# SNAC_7ch_hdmi-5v.net
KiCad netlist of a schematic drawn in EAGLE
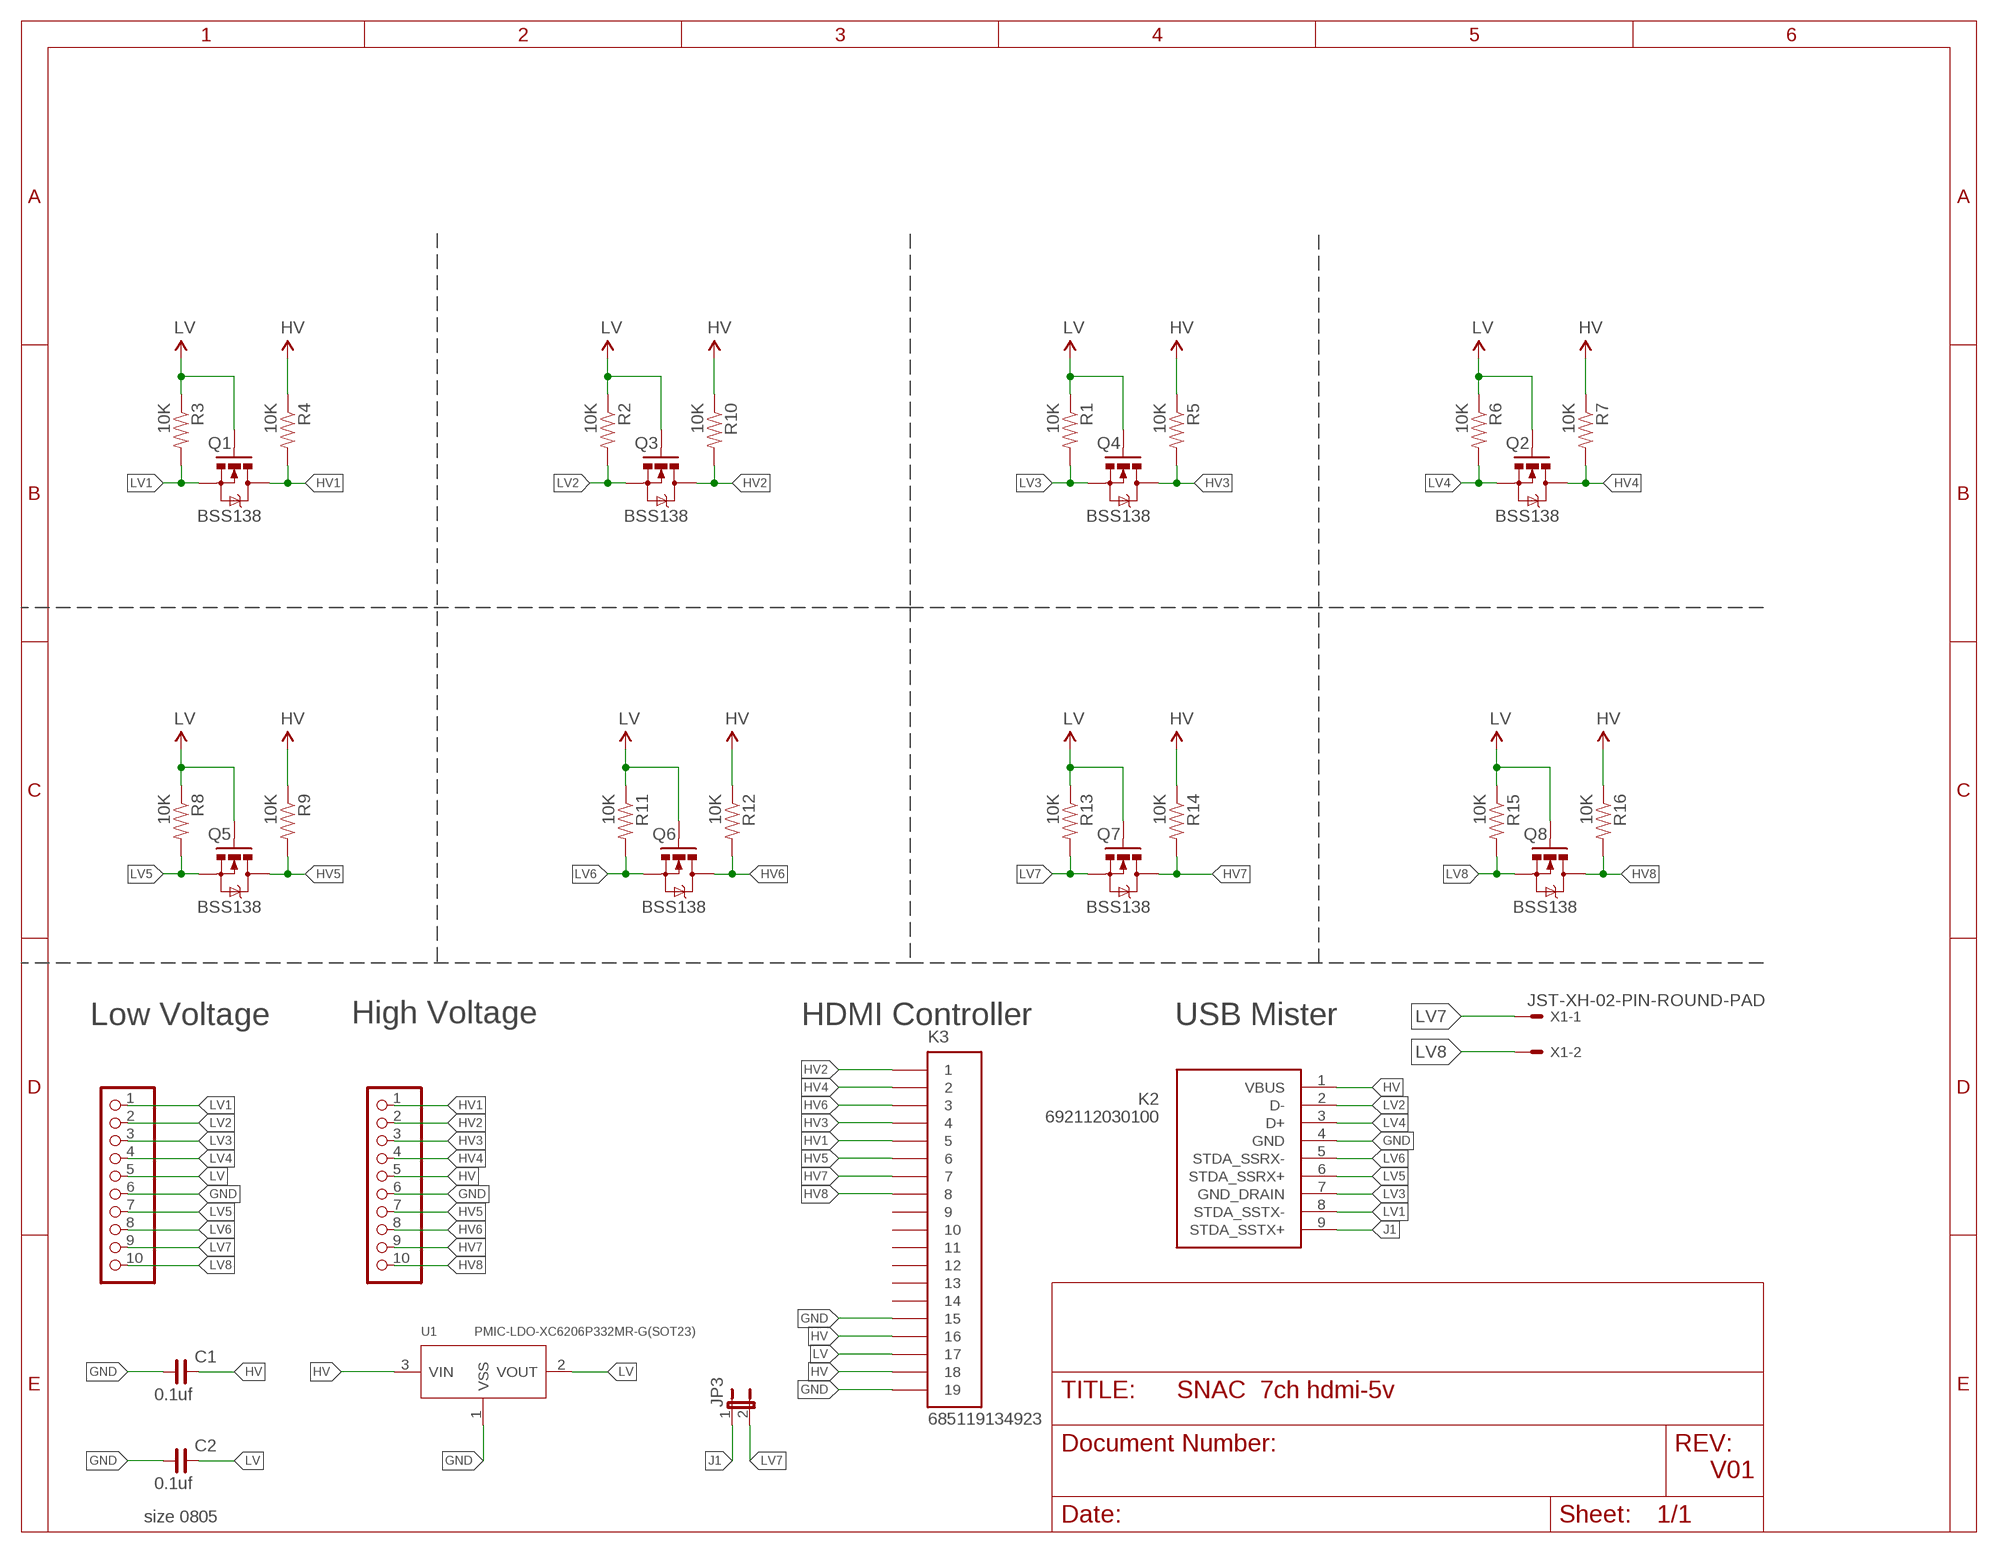
[diagram p0: schematic, sheet 1]

(export (version "E")
  (design (tool "Eeschema 10.0.6"))
  (components
    (comp (ref "C1")
      (value "0.1uf")
      (footprint "eagle-import:C0805")
      (libsource (lib "eagle-import") (part "C_0805"))
    )
    (comp (ref "C2")
      (value "0.1uf")
      (footprint "eagle-import:C0805")
      (libsource (lib "eagle-import") (part "C_0805"))
    )
    (comp (ref "JP1")
      (value "PINHD-1X10_2.54-S")
      (footprint "eagle-import:1X10-S")
      (libsource (lib "eagle-import") (part "PINHD-1X10_2.54-S"))
    )
    (comp (ref "JP2")
      (value "PINHD-1X10_2.54-S")
      (footprint "eagle-import:1X10-S")
      (libsource (lib "eagle-import") (part "PINHD-1X10_2.54-S"))
    )
    (comp (ref "JP3")
      (value "JUMPER-2PTH")
      (footprint "eagle-import:1X02")
      (libsource (lib "eagle-import") (part "JUMPER-2PTH"))
    )
    (comp (ref "K2")
      (value "692112030100")
      (footprint "eagle-import:692112030100")
      (libsource (lib "eagle-import") (part "692112030100"))
    )
    (comp (ref "K3")
      (value "685119134923")
      (footprint "eagle-import:685119134923")
      (libsource (lib "eagle-import") (part "685119134923"))
    )
    (comp (ref "Q1")
      (value "BSS138")
      (footprint "eagle-import:SOT23-3")
      (libsource (lib "eagle-import") (part "MOSFET-NCHANNELSMD"))
    )
    (comp (ref "Q2")
      (value "BSS138")
      (footprint "eagle-import:SOT23-3")
      (libsource (lib "eagle-import") (part "MOSFET-NCHANNELSMD"))
    )
    (comp (ref "Q3")
      (value "BSS138")
      (footprint "eagle-import:SOT23-3")
      (libsource (lib "eagle-import") (part "MOSFET-NCHANNELSMD"))
    )
    (comp (ref "Q4")
      (value "BSS138")
      (footprint "eagle-import:SOT23-3")
      (libsource (lib "eagle-import") (part "MOSFET-NCHANNELSMD"))
    )
    (comp (ref "Q5")
      (value "BSS138")
      (footprint "eagle-import:SOT23-3")
      (libsource (lib "eagle-import") (part "MOSFET-NCHANNELSMD"))
    )
    (comp (ref "Q6")
      (value "BSS138")
      (footprint "eagle-import:SOT23-3")
      (libsource (lib "eagle-import") (part "MOSFET-NCHANNELSMD"))
    )
    (comp (ref "Q7")
      (value "BSS138")
      (footprint "eagle-import:SOT23-3")
      (libsource (lib "eagle-import") (part "MOSFET-NCHANNELSMD"))
    )
    (comp (ref "Q8")
      (value "BSS138")
      (footprint "eagle-import:SOT23-3")
      (libsource (lib "eagle-import") (part "MOSFET-NCHANNELSMD"))
    )
    (comp (ref "R1")
      (value "10K")
      (footprint "eagle-import:0603-RES")
      (libsource (lib "eagle-import") (part "RESISTOR0603-RES"))
    )
    (comp (ref "R2")
      (value "10K")
      (footprint "eagle-import:0603-RES")
      (libsource (lib "eagle-import") (part "RESISTOR0603-RES"))
    )
    (comp (ref "R3")
      (value "10K")
      (footprint "eagle-import:0603-RES")
      (libsource (lib "eagle-import") (part "RESISTOR0603-RES"))
    )
    (comp (ref "R4")
      (value "10K")
      (footprint "eagle-import:0603-RES")
      (libsource (lib "eagle-import") (part "RESISTOR0603-RES"))
    )
    (comp (ref "R5")
      (value "10K")
      (footprint "eagle-import:0603-RES")
      (libsource (lib "eagle-import") (part "RESISTOR0603-RES"))
    )
    (comp (ref "R6")
      (value "10K")
      (footprint "eagle-import:0603-RES")
      (libsource (lib "eagle-import") (part "RESISTOR0603-RES"))
    )
    (comp (ref "R7")
      (value "10K")
      (footprint "eagle-import:0603-RES")
      (libsource (lib "eagle-import") (part "RESISTOR0603-RES"))
    )
    (comp (ref "R8")
      (value "10K")
      (footprint "eagle-import:0603-RES")
      (libsource (lib "eagle-import") (part "RESISTOR0603-RES"))
    )
    (comp (ref "R9")
      (value "10K")
      (footprint "eagle-import:0603-RES")
      (libsource (lib "eagle-import") (part "RESISTOR0603-RES"))
    )
    (comp (ref "R10")
      (value "10K")
      (footprint "eagle-import:0603-RES")
      (libsource (lib "eagle-import") (part "RESISTOR0603-RES"))
    )
    (comp (ref "R11")
      (value "10K")
      (footprint "eagle-import:0603-RES")
      (libsource (lib "eagle-import") (part "RESISTOR0603-RES"))
    )
    (comp (ref "R12")
      (value "10K")
      (footprint "eagle-import:0603-RES")
      (libsource (lib "eagle-import") (part "RESISTOR0603-RES"))
    )
    (comp (ref "R13")
      (value "10K")
      (footprint "eagle-import:0603-RES")
      (libsource (lib "eagle-import") (part "RESISTOR0603-RES"))
    )
    (comp (ref "R14")
      (value "10K")
      (footprint "eagle-import:0603-RES")
      (libsource (lib "eagle-import") (part "RESISTOR0603-RES"))
    )
    (comp (ref "R15")
      (value "10K")
      (footprint "eagle-import:0603-RES")
      (libsource (lib "eagle-import") (part "RESISTOR0603-RES"))
    )
    (comp (ref "R16")
      (value "10K")
      (footprint "eagle-import:0603-RES")
      (libsource (lib "eagle-import") (part "RESISTOR0603-RES"))
    )
    (comp (ref "U1")
      (value "PMIC-LDO-XC6206P332MR-G(SOT23)")
      (footprint "eagle-import:SOT-23")
      (fields (field (name "MF") "Torex") (field (name "MP") "XC6206P332MR-G"))
      (libsource (lib "eagle-import") (part "PMIC-LDO-XC6206P332MR-G(SOT23)"))
    )
    (comp (ref "X1")
      (value "JST-XH-02-PIN-ROUND-PAD")
      (footprint "eagle-import:JST-XH-02-PACKAGE-ROUND-PAD")
      (libsource (lib "eagle-import") (part "JST-XH-02-PIN-ROUND-PAD"))
    )
  )
  (nets
    (net (code "1") (name "GND") (class "Default")
      (node (ref "C1") (pin "1") (pinfunction "1_1") (pintype "passive"))
      (node (ref "C2") (pin "1") (pinfunction "1_1") (pintype "passive"))
      (node (ref "JP1") (pin "6") (pinfunction "6_6") (pintype "passive"))
      (node (ref "JP2") (pin "6") (pinfunction "6_6") (pintype "passive"))
      (node (ref "K2") (pin "4") (pinfunction "GND_4") (pintype "bidirectional"))
      (node (ref "K3") (pin "15") (pinfunction "15_15") (pintype "passive"))
      (node (ref "K3") (pin "19") (pinfunction "19_19") (pintype "passive"))
      (node (ref "U1") (pin "1") (pinfunction "VSS_1") (pintype "power_in"))
    )
    (net (code "2") (name "HV") (class "Default")
      (node (ref "C1") (pin "2") (pinfunction "2_2") (pintype "passive"))
      (node (ref "JP2") (pin "5") (pinfunction "5_5") (pintype "passive"))
      (node (ref "K2") (pin "1") (pinfunction "VBUS_1") (pintype "bidirectional"))
      (node (ref "K3") (pin "16") (pinfunction "16_16") (pintype "passive"))
      (node (ref "K3") (pin "18") (pinfunction "18_18") (pintype "passive"))
      (node (ref "R10") (pin "1") (pinfunction "1_1") (pintype "passive"))
      (node (ref "R12") (pin "1") (pinfunction "1_1") (pintype "passive"))
      (node (ref "R14") (pin "1") (pinfunction "1_1") (pintype "passive"))
      (node (ref "R16") (pin "1") (pinfunction "1_1") (pintype "passive"))
      (node (ref "R4") (pin "1") (pinfunction "1_1") (pintype "passive"))
      (node (ref "R5") (pin "1") (pinfunction "1_1") (pintype "passive"))
      (node (ref "R7") (pin "1") (pinfunction "1_1") (pintype "passive"))
      (node (ref "R9") (pin "1") (pinfunction "1_1") (pintype "passive"))
      (node (ref "U1") (pin "3") (pinfunction "VIN_3") (pintype "input"))
    )
    (net (code "3") (name "HV1") (class "Default")
      (node (ref "JP2") (pin "1") (pinfunction "1_1") (pintype "passive"))
      (node (ref "K3") (pin "5") (pinfunction "5_5") (pintype "passive"))
      (node (ref "Q1") (pin "3") (pinfunction "D_3") (pintype "passive"))
      (node (ref "R4") (pin "2") (pinfunction "2_2") (pintype "passive"))
    )
    (net (code "4") (name "HV2") (class "Default")
      (node (ref "JP2") (pin "2") (pinfunction "2_2") (pintype "passive"))
      (node (ref "K3") (pin "1") (pinfunction "1_1") (pintype "passive"))
      (node (ref "Q3") (pin "3") (pinfunction "D_3") (pintype "passive"))
      (node (ref "R10") (pin "2") (pinfunction "2_2") (pintype "passive"))
    )
    (net (code "5") (name "HV3") (class "Default")
      (node (ref "JP2") (pin "3") (pinfunction "3_3") (pintype "passive"))
      (node (ref "K3") (pin "4") (pinfunction "4_4") (pintype "passive"))
      (node (ref "Q4") (pin "3") (pinfunction "D_3") (pintype "passive"))
      (node (ref "R5") (pin "2") (pinfunction "2_2") (pintype "passive"))
    )
    (net (code "6") (name "HV4") (class "Default")
      (node (ref "JP2") (pin "4") (pinfunction "4_4") (pintype "passive"))
      (node (ref "K3") (pin "2") (pinfunction "2_2") (pintype "passive"))
      (node (ref "Q2") (pin "3") (pinfunction "D_3") (pintype "passive"))
      (node (ref "R7") (pin "2") (pinfunction "2_2") (pintype "passive"))
    )
    (net (code "7") (name "HV5") (class "Default")
      (node (ref "JP2") (pin "7") (pinfunction "7_7") (pintype "passive"))
      (node (ref "K3") (pin "6") (pinfunction "6_6") (pintype "passive"))
      (node (ref "Q5") (pin "3") (pinfunction "D_3") (pintype "passive"))
      (node (ref "R9") (pin "2") (pinfunction "2_2") (pintype "passive"))
    )
    (net (code "8") (name "HV6") (class "Default")
      (node (ref "JP2") (pin "8") (pinfunction "8_8") (pintype "passive"))
      (node (ref "K3") (pin "3") (pinfunction "3_3") (pintype "passive"))
      (node (ref "Q6") (pin "3") (pinfunction "D_3") (pintype "passive"))
      (node (ref "R12") (pin "2") (pinfunction "2_2") (pintype "passive"))
    )
    (net (code "9") (name "HV7") (class "Default")
      (node (ref "JP2") (pin "9") (pinfunction "9_9") (pintype "passive"))
      (node (ref "K3") (pin "7") (pinfunction "7_7") (pintype "passive"))
      (node (ref "Q7") (pin "3") (pinfunction "D_3") (pintype "passive"))
      (node (ref "R14") (pin "2") (pinfunction "2_2") (pintype "passive"))
    )
    (net (code "10") (name "HV8") (class "Default")
      (node (ref "JP2") (pin "10") (pinfunction "10_10") (pintype "passive"))
      (node (ref "K3") (pin "8") (pinfunction "8_8") (pintype "passive"))
      (node (ref "Q8") (pin "3") (pinfunction "D_3") (pintype "passive"))
      (node (ref "R16") (pin "2") (pinfunction "2_2") (pintype "passive"))
    )
    (net (code "11") (name "J1") (class "Default")
      (node (ref "JP3") (pin "1") (pinfunction "1_1") (pintype "passive"))
      (node (ref "K2") (pin "9") (pinfunction "STDA_SSTX+_9") (pintype "bidirectional"))
    )
    (net (code "12") (name "LV") (class "Default")
      (node (ref "C2") (pin "2") (pinfunction "2_2") (pintype "passive"))
      (node (ref "JP1") (pin "5") (pinfunction "5_5") (pintype "passive"))
      (node (ref "K3") (pin "17") (pinfunction "17_17") (pintype "passive"))
      (node (ref "Q1") (pin "1") (pinfunction "G_1") (pintype "passive"))
      (node (ref "Q2") (pin "1") (pinfunction "G_1") (pintype "passive"))
      (node (ref "Q3") (pin "1") (pinfunction "G_1") (pintype "passive"))
      (node (ref "Q4") (pin "1") (pinfunction "G_1") (pintype "passive"))
      (node (ref "Q5") (pin "1") (pinfunction "G_1") (pintype "passive"))
      (node (ref "Q6") (pin "1") (pinfunction "G_1") (pintype "passive"))
      (node (ref "Q7") (pin "1") (pinfunction "G_1") (pintype "passive"))
      (node (ref "Q8") (pin "1") (pinfunction "G_1") (pintype "passive"))
      (node (ref "R1") (pin "1") (pinfunction "1_1") (pintype "passive"))
      (node (ref "R11") (pin "1") (pinfunction "1_1") (pintype "passive"))
      (node (ref "R13") (pin "1") (pinfunction "1_1") (pintype "passive"))
      (node (ref "R15") (pin "1") (pinfunction "1_1") (pintype "passive"))
      (node (ref "R2") (pin "1") (pinfunction "1_1") (pintype "passive"))
      (node (ref "R3") (pin "1") (pinfunction "1_1") (pintype "passive"))
      (node (ref "R6") (pin "1") (pinfunction "1_1") (pintype "passive"))
      (node (ref "R8") (pin "1") (pinfunction "1_1") (pintype "passive"))
      (node (ref "U1") (pin "2") (pinfunction "VOUT_2") (pintype "output"))
    )
    (net (code "13") (name "LV1") (class "Default")
      (node (ref "JP1") (pin "1") (pinfunction "1_1") (pintype "passive"))
      (node (ref "K2") (pin "8") (pinfunction "STDA_SSTX-_8") (pintype "bidirectional"))
      (node (ref "Q1") (pin "2") (pinfunction "S_2") (pintype "passive"))
      (node (ref "R3") (pin "2") (pinfunction "2_2") (pintype "passive"))
    )
    (net (code "14") (name "LV2") (class "Default")
      (node (ref "JP1") (pin "2") (pinfunction "2_2") (pintype "passive"))
      (node (ref "K2") (pin "2") (pinfunction "D-_2") (pintype "bidirectional"))
      (node (ref "Q3") (pin "2") (pinfunction "S_2") (pintype "passive"))
      (node (ref "R2") (pin "2") (pinfunction "2_2") (pintype "passive"))
    )
    (net (code "15") (name "LV3") (class "Default")
      (node (ref "JP1") (pin "3") (pinfunction "3_3") (pintype "passive"))
      (node (ref "K2") (pin "7") (pinfunction "GND_DRAIN_7") (pintype "bidirectional"))
      (node (ref "Q4") (pin "2") (pinfunction "S_2") (pintype "passive"))
      (node (ref "R1") (pin "2") (pinfunction "2_2") (pintype "passive"))
    )
    (net (code "16") (name "LV4") (class "Default")
      (node (ref "JP1") (pin "4") (pinfunction "4_4") (pintype "passive"))
      (node (ref "K2") (pin "3") (pinfunction "D+_3") (pintype "bidirectional"))
      (node (ref "Q2") (pin "2") (pinfunction "S_2") (pintype "passive"))
      (node (ref "R6") (pin "2") (pinfunction "2_2") (pintype "passive"))
    )
    (net (code "17") (name "LV5") (class "Default")
      (node (ref "JP1") (pin "7") (pinfunction "7_7") (pintype "passive"))
      (node (ref "K2") (pin "6") (pinfunction "STDA_SSRX+_6") (pintype "bidirectional"))
      (node (ref "Q5") (pin "2") (pinfunction "S_2") (pintype "passive"))
      (node (ref "R8") (pin "2") (pinfunction "2_2") (pintype "passive"))
    )
    (net (code "18") (name "LV6") (class "Default")
      (node (ref "JP1") (pin "8") (pinfunction "8_8") (pintype "passive"))
      (node (ref "K2") (pin "5") (pinfunction "STDA_SSRX-_5") (pintype "bidirectional"))
      (node (ref "Q6") (pin "2") (pinfunction "S_2") (pintype "passive"))
      (node (ref "R11") (pin "2") (pinfunction "2_2") (pintype "passive"))
    )
    (net (code "19") (name "LV7") (class "Default")
      (node (ref "JP1") (pin "9") (pinfunction "9_9") (pintype "passive"))
      (node (ref "JP3") (pin "2") (pinfunction "2_2") (pintype "passive"))
      (node (ref "Q7") (pin "2") (pinfunction "S_2") (pintype "passive"))
      (node (ref "R13") (pin "2") (pinfunction "2_2") (pintype "passive"))
      (node (ref "X1") (pin "1") (pinfunction "S_1") (pintype "passive"))
    )
    (net (code "20") (name "LV8") (class "Default")
      (node (ref "JP1") (pin "10") (pinfunction "10_10") (pintype "passive"))
      (node (ref "Q8") (pin "2") (pinfunction "S_2") (pintype "passive"))
      (node (ref "R15") (pin "2") (pinfunction "2_2") (pintype "passive"))
      (node (ref "X1") (pin "2") (pinfunction "S_2") (pintype "passive"))
    )
    (net (code "21") (name "unconnected-(K3-Pad9)") (class "Default")
      (node (ref "K3") (pin "9") (pinfunction "9_9") (pintype "passive"))
    )
    (net (code "22") (name "unconnected-(K3-Pad10)") (class "Default")
      (node (ref "K3") (pin "10") (pinfunction "10_10") (pintype "passive"))
    )
    (net (code "23") (name "unconnected-(K3-Pad11)") (class "Default")
      (node (ref "K3") (pin "11") (pinfunction "11_11") (pintype "passive"))
    )
    (net (code "24") (name "unconnected-(K3-Pad12)") (class "Default")
      (node (ref "K3") (pin "12") (pinfunction "12_12") (pintype "passive"))
    )
    (net (code "25") (name "unconnected-(K3-Pad13)") (class "Default")
      (node (ref "K3") (pin "13") (pinfunction "13_13") (pintype "passive"))
    )
    (net (code "26") (name "unconnected-(K3-Pad14)") (class "Default")
      (node (ref "K3") (pin "14") (pinfunction "14_14") (pintype "passive"))
    )
  )
)
